# DAQ_IO.net
KiCad netlist of a schematic drawn in Altium Designer
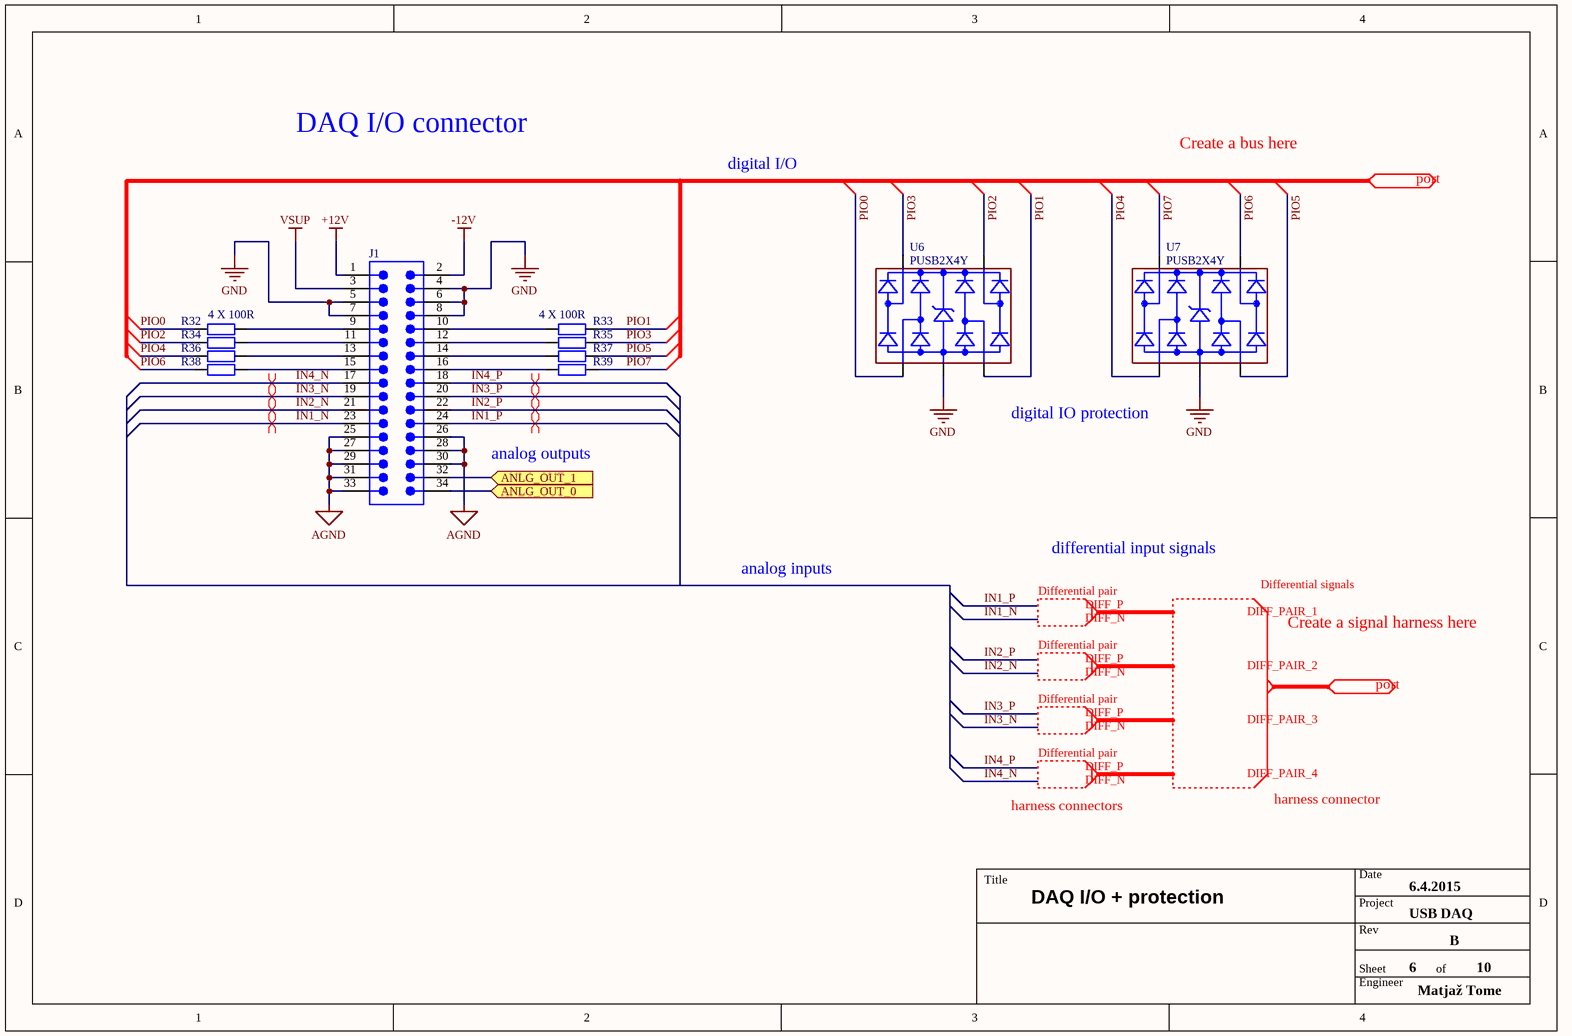
[diagram p0: DAQ_IO.SchDoc]

(export (version "E")
  (design (tool "Eeschema 10.0.6"))
  (components
    (comp (ref "J1")
      (value "2X17")
      (footprint "IDC34R")
      (description "Pin Header, Right Angle, Wire-to-Board, 2.54 mm, 2 Rows, 34 Contacts, Through Hole Right Angle")
      (fields (field (name "MANUFACTURER") "Harting"))
      (libsource (lib "DAQ_REV_B") (part "09 18 534 7323"))
    )
    (comp (ref "R32")
      (value "100R")
      (footprint "R_0603")
      (description "Generic resistor")
      (libsource (lib "DAQ_REV_B") (part "Resistor"))
    )
    (comp (ref "R33")
      (value "100R")
      (footprint "R_0603")
      (description "Generic resistor")
      (libsource (lib "DAQ_REV_B") (part "Resistor"))
    )
    (comp (ref "R34")
      (value "100R")
      (footprint "R_0603")
      (description "Generic resistor")
      (libsource (lib "DAQ_REV_B") (part "Resistor"))
    )
    (comp (ref "R35")
      (value "100R")
      (footprint "R_0603")
      (description "Generic resistor")
      (libsource (lib "DAQ_REV_B") (part "Resistor"))
    )
    (comp (ref "R36")
      (value "100R")
      (footprint "R_0603")
      (description "Generic resistor")
      (libsource (lib "DAQ_REV_B") (part "Resistor"))
    )
    (comp (ref "R37")
      (value "100R")
      (footprint "R_0603")
      (description "Generic resistor")
      (libsource (lib "DAQ_REV_B") (part "Resistor"))
    )
    (comp (ref "R38")
      (value "100R")
      (footprint "R_0603")
      (description "Generic resistor")
      (libsource (lib "DAQ_REV_B") (part "Resistor"))
    )
    (comp (ref "R39")
      (value "100R")
      (footprint "R_0603")
      (description "Generic resistor")
      (libsource (lib "DAQ_REV_B") (part "Resistor"))
    )
    (comp (ref "U6")
      (value "PUSB2X4Y")
      (footprint "SOT363")
      (description "ESD protection for high-speed interfaces")
      (fields (field (name "PART NUMBER") "XDE0000") (field (name "MANUFACTURER") "Multicomp"))
      (libsource (lib "DAQ_REV_B") (part "PUSB2X4Y"))
    )
    (comp (ref "U7")
      (value "PUSB2X4Y")
      (footprint "SOT363")
      (description "ESD protection for high-speed interfaces")
      (fields (field (name "PART NUMBER") "XDE0000") (field (name "MANUFACTURER") "Multicomp"))
      (libsource (lib "DAQ_REV_B") (part "PUSB2X4Y"))
    )
  )
  (nets
    (net (code "1") (name "+12V") (class "Default")
      (node (ref "J1") (pin "1") (pinfunction "1_1") (pintype "passive"))
    )
    (net (code "2") (name "-12V") (class "Default")
      (node (ref "J1") (pin "2") (pinfunction "2_2") (pintype "passive"))
    )
    (net (code "3") (name "/ANLG_OUT_0") (class "Default")
      (node (ref "J1") (pin "34") (pinfunction "34_34") (pintype "passive"))
    )
    (net (code "4") (name "/ANLG_OUT_1") (class "Default")
      (node (ref "J1") (pin "32") (pinfunction "32_32") (pintype "passive"))
    )
    (net (code "5") (name "/IN1_N") (class "Default")
      (node (ref "J1") (pin "23") (pinfunction "23_23") (pintype "passive"))
    )
    (net (code "6") (name "/IN1_P") (class "Default")
      (node (ref "J1") (pin "24") (pinfunction "24_24") (pintype "passive"))
    )
    (net (code "7") (name "/IN2_N") (class "Default")
      (node (ref "J1") (pin "21") (pinfunction "21_21") (pintype "passive"))
    )
    (net (code "8") (name "/IN2_P") (class "Default")
      (node (ref "J1") (pin "22") (pinfunction "22_22") (pintype "passive"))
    )
    (net (code "9") (name "/IN3_N") (class "Default")
      (node (ref "J1") (pin "19") (pinfunction "19_19") (pintype "passive"))
    )
    (net (code "10") (name "/IN3_P") (class "Default")
      (node (ref "J1") (pin "20") (pinfunction "20_20") (pintype "passive"))
    )
    (net (code "11") (name "/IN4_N") (class "Default")
      (node (ref "J1") (pin "17") (pinfunction "17_17") (pintype "passive"))
    )
    (net (code "12") (name "/IN4_P") (class "Default")
      (node (ref "J1") (pin "18") (pinfunction "18_18") (pintype "passive"))
    )
    (net (code "13") (name "/PIO0") (class "Default")
      (node (ref "R32") (pin "1") (pintype "passive"))
      (node (ref "U6") (pin "1") (pinfunction "1_1") (pintype "passive"))
    )
    (net (code "14") (name "/PIO1") (class "Default")
      (node (ref "R33") (pin "2") (pintype "passive"))
      (node (ref "U6") (pin "3") (pinfunction "3_3") (pintype "passive"))
    )
    (net (code "15") (name "/PIO2") (class "Default")
      (node (ref "R34") (pin "1") (pintype "passive"))
      (node (ref "U6") (pin "4") (pinfunction "4_4") (pintype "passive"))
    )
    (net (code "16") (name "/PIO3") (class "Default")
      (node (ref "R35") (pin "2") (pintype "passive"))
      (node (ref "U6") (pin "6") (pinfunction "6_6") (pintype "passive"))
    )
    (net (code "17") (name "/PIO4") (class "Default")
      (node (ref "R36") (pin "1") (pintype "passive"))
      (node (ref "U7") (pin "1") (pinfunction "1_1") (pintype "passive"))
    )
    (net (code "18") (name "/PIO5") (class "Default")
      (node (ref "R37") (pin "2") (pintype "passive"))
      (node (ref "U7") (pin "3") (pinfunction "3_3") (pintype "passive"))
    )
    (net (code "19") (name "/PIO6") (class "Default")
      (node (ref "R38") (pin "1") (pintype "passive"))
      (node (ref "U7") (pin "4") (pinfunction "4_4") (pintype "passive"))
    )
    (net (code "20") (name "/PIO7") (class "Default")
      (node (ref "R39") (pin "2") (pintype "passive"))
      (node (ref "U7") (pin "6") (pinfunction "6_6") (pintype "passive"))
    )
    (net (code "21") (name "AGND") (class "Default")
      (node (ref "J1") (pin "25") (pinfunction "25_25") (pintype "passive"))
      (node (ref "J1") (pin "26") (pinfunction "26_26") (pintype "passive"))
      (node (ref "J1") (pin "27") (pinfunction "27_27") (pintype "passive"))
      (node (ref "J1") (pin "28") (pinfunction "28_28") (pintype "passive"))
      (node (ref "J1") (pin "29") (pinfunction "29_29") (pintype "passive"))
      (node (ref "J1") (pin "30") (pinfunction "30_30") (pintype "passive"))
      (node (ref "J1") (pin "31") (pinfunction "31_31") (pintype "passive"))
      (node (ref "J1") (pin "33") (pinfunction "33_33") (pintype "passive"))
    )
    (net (code "22") (name "GND") (class "Default")
      (node (ref "J1") (pin "4") (pinfunction "4_4") (pintype "passive"))
      (node (ref "J1") (pin "5") (pinfunction "5_5") (pintype "passive"))
      (node (ref "J1") (pin "6") (pinfunction "6_6") (pintype "passive"))
      (node (ref "J1") (pin "7") (pinfunction "7_7") (pintype "passive"))
      (node (ref "J1") (pin "8") (pinfunction "8_8") (pintype "passive"))
      (node (ref "U6") (pin "2") (pinfunction "2_2") (pintype "passive"))
      (node (ref "U7") (pin "2") (pinfunction "2_2") (pintype "passive"))
    )
    (net (code "23") (name "Net-(J1-Pad9)") (class "Default")
      (node (ref "J1") (pin "9") (pinfunction "9_9") (pintype "passive"))
      (node (ref "R32") (pin "2") (pintype "passive"))
    )
    (net (code "24") (name "Net-(J1-Pad10)") (class "Default")
      (node (ref "J1") (pin "10") (pinfunction "10_10") (pintype "passive"))
      (node (ref "R33") (pin "1") (pintype "passive"))
    )
    (net (code "25") (name "Net-(J1-Pad11)") (class "Default")
      (node (ref "J1") (pin "11") (pinfunction "11_11") (pintype "passive"))
      (node (ref "R34") (pin "2") (pintype "passive"))
    )
    (net (code "26") (name "Net-(J1-Pad12)") (class "Default")
      (node (ref "J1") (pin "12") (pinfunction "12_12") (pintype "passive"))
      (node (ref "R35") (pin "1") (pintype "passive"))
    )
    (net (code "27") (name "Net-(J1-Pad13)") (class "Default")
      (node (ref "J1") (pin "13") (pinfunction "13_13") (pintype "passive"))
      (node (ref "R36") (pin "2") (pintype "passive"))
    )
    (net (code "28") (name "Net-(J1-Pad14)") (class "Default")
      (node (ref "J1") (pin "14") (pinfunction "14_14") (pintype "passive"))
      (node (ref "R37") (pin "1") (pintype "passive"))
    )
    (net (code "29") (name "Net-(J1-Pad15)") (class "Default")
      (node (ref "J1") (pin "15") (pinfunction "15_15") (pintype "passive"))
      (node (ref "R38") (pin "2") (pintype "passive"))
    )
    (net (code "30") (name "Net-(J1-Pad16)") (class "Default")
      (node (ref "J1") (pin "16") (pinfunction "16_16") (pintype "passive"))
      (node (ref "R39") (pin "1") (pintype "passive"))
    )
    (net (code "31") (name "VSUP") (class "Default")
      (node (ref "J1") (pin "3") (pinfunction "3_3") (pintype "passive"))
    )
  )
)
